# tricorder-featherwing-mk-1_6.net
KiCad netlist of a schematic drawn in EAGLE
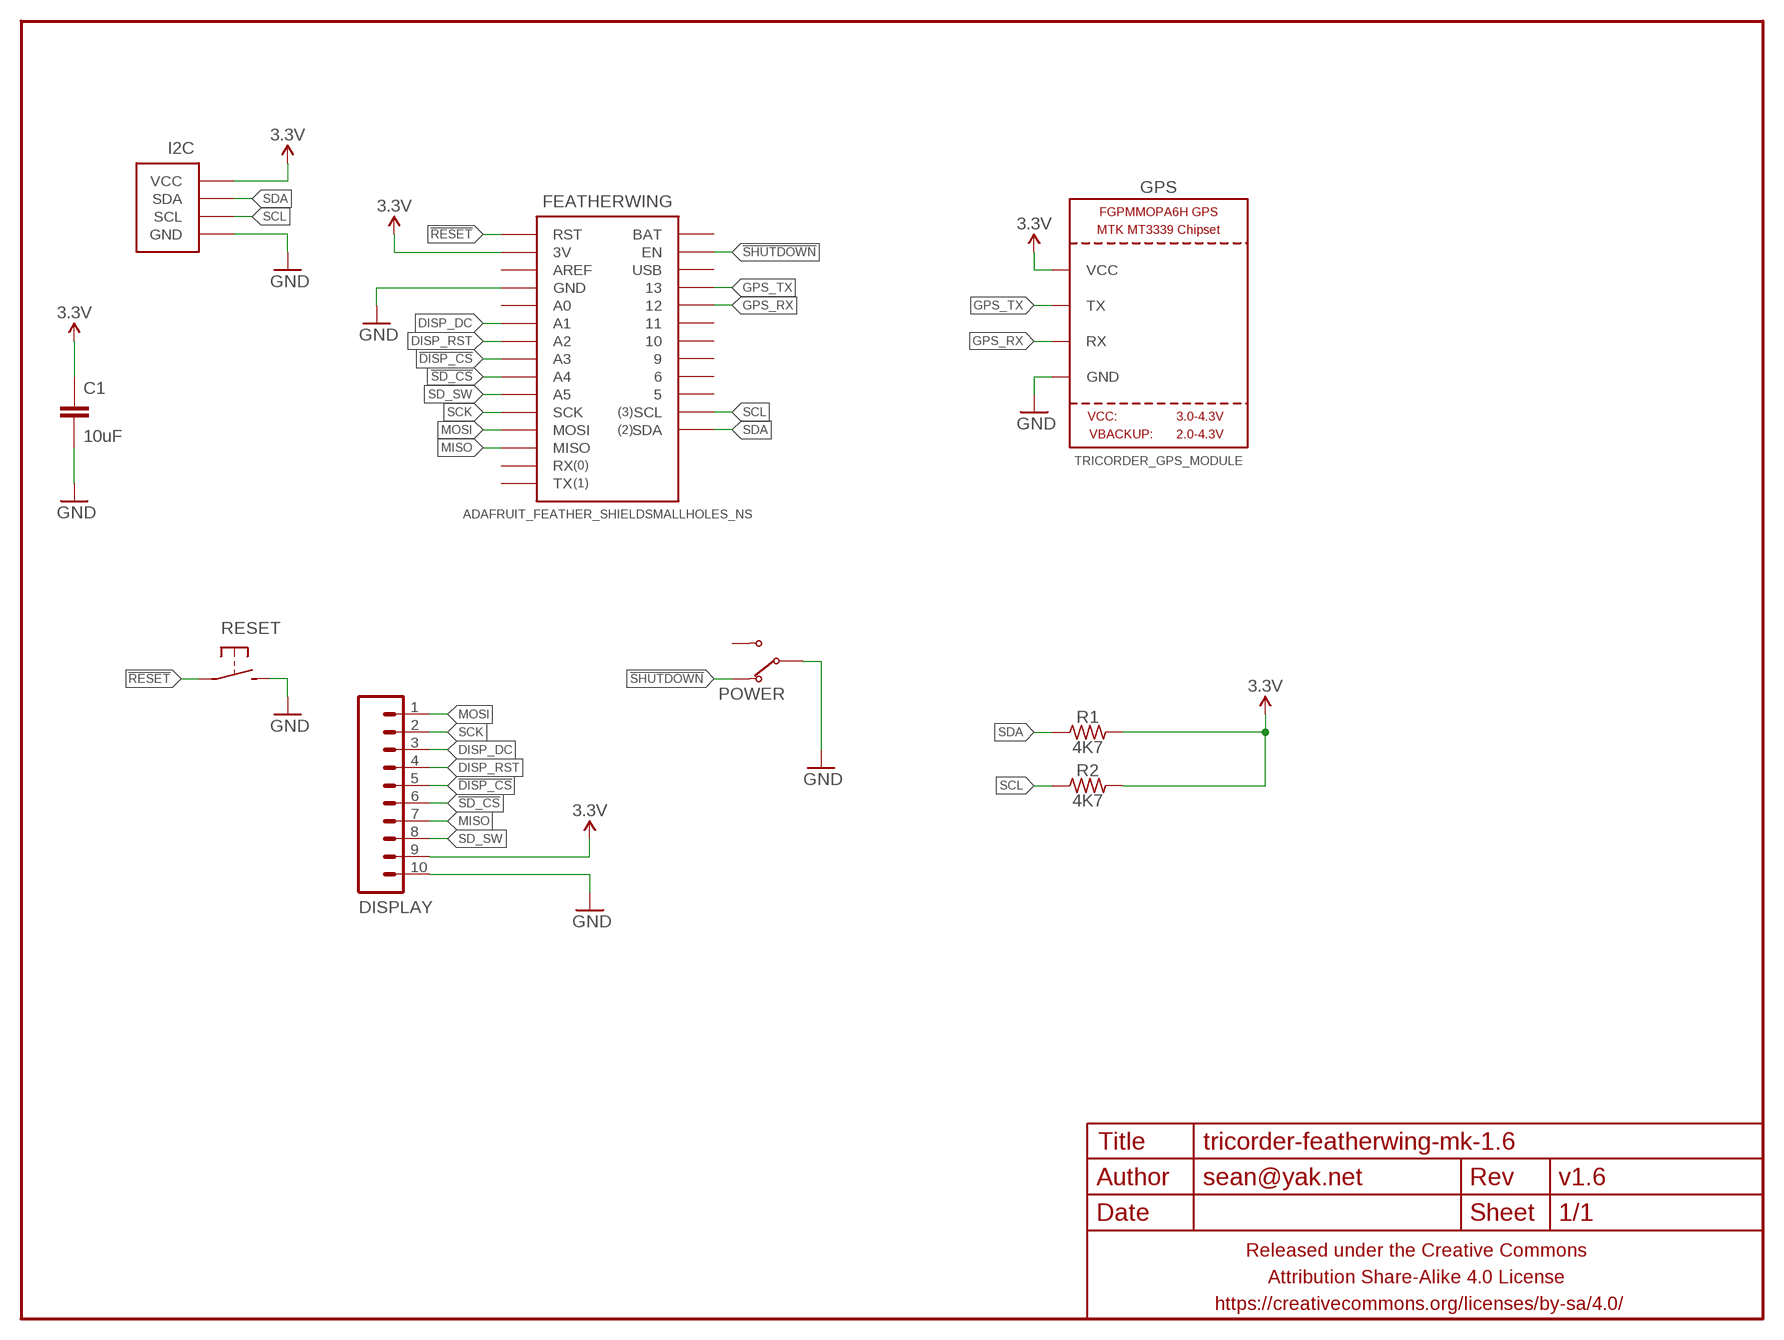
[diagram p0: schematic, sheet 1]

(export (version "E")
  (design (tool "Eeschema 10.0.6"))
  (components
    (comp (ref "C1")
      (value "10uF")
      (footprint "eagle-import:C1210")
      (libsource (lib "eagle-import") (part "CAPACITOR-CERAMICC1210"))
    )
    (comp (ref "DISPLAY")
      (value "M102MM")
      (footprint "eagle-import:1X10-2MM")
      (libsource (lib "eagle-import") (part "M102MM"))
    )
    (comp (ref "FEATHERWING")
      (value "ADAFRUIT_FEATHER_SHIELDSMALLHOLES_NS")
      (footprint "eagle-import:ADAFRUIT_FEATHER_SMALLHOLES_NS")
      (libsource (lib "eagle-import") (part "ADAFRUIT_FEATHER_SHIELDSMALLHOLES_NS"))
    )
    (comp (ref "FRAME1")
      (value "FRAME-LETTERNO_PACKAGE")
      (footprint "eagle-import:DUMMY")
      (fields (field (name "DESIGNER") "sean@yak.net") (field (name "VERSION") "v1.6"))
      (libsource (lib "eagle-import") (part "FRAME-LETTERNO_PACKAGE"))
    )
    (comp (ref "GPS")
      (value "TRICORDER_GPS_MODULE")
      (footprint "eagle-import:TRICORDER_GPS_MODULE")
      (libsource (lib "eagle-import") (part "TRICORDER_GPS_MODULE"))
    )
    (comp (ref "I2C")
      (value "M04-I2CPTH-2MM-CENTERED")
      (footprint "eagle-import:1X04-2MM-CENTERED-I2C")
      (libsource (lib "eagle-import") (part "M04-I2CPTH-2MM-CENTERED"))
    )
    (comp (ref "POWER")
      (value "SWITCH-SPDTPTH-RA-2.54MM-CENTERED")
      (footprint "eagle-import:SPDT-RA-2.54MM-CENTERED")
      (libsource (lib "eagle-import") (part "SWITCH-SPDTPTH-RA-2.54MM-CENTERED"))
    )
    (comp (ref "R1")
      (value "4K7")
      (footprint "eagle-import:R0603")
      (libsource (lib "eagle-import") (part "RESISTORR0603"))
    )
    (comp (ref "R2")
      (value "4K7")
      (footprint "eagle-import:R0603")
      (libsource (lib "eagle-import") (part "RESISTORR0603"))
    )
    (comp (ref "RESET")
      (value "SPST-NO-TACTCK-PTS840-GK")
      (footprint "eagle-import:TACTILE-SMD-CK-PTS840-GK")
      (libsource (lib "eagle-import") (part "SPST-NO-TACTCK-PTS840-GK"))
    )
  )
  (nets
    (net (code "1") (name "/~{DISP_CS}") (class "Default")
      (node (ref "DISPLAY") (pin "5") (pinfunction "5_5") (pintype "passive"))
      (node (ref "FEATHERWING") (pin "A3") (pinfunction "A3_A3") (pintype "bidirectional"))
    )
    (net (code "2") (name "/~{RESET}") (class "Default")
      (node (ref "FEATHERWING") (pin "RST") (pinfunction "RST_RST") (pintype "bidirectional"))
      (node (ref "RESET") (pin "1") (pinfunction "1_1") (pintype "passive"))
      (node (ref "RESET") (pin "2") (pinfunction "1_2") (pintype "passive"))
    )
    (net (code "3") (name "/~{SD_CS}") (class "Default")
      (node (ref "DISPLAY") (pin "6") (pinfunction "6_6") (pintype "passive"))
      (node (ref "FEATHERWING") (pin "A4") (pinfunction "A4_A4") (pintype "bidirectional"))
    )
    (net (code "4") (name "/~{SHUTDOWN}") (class "Default")
      (node (ref "FEATHERWING") (pin "EN") (pinfunction "EN_EN") (pintype "bidirectional"))
      (node (ref "POWER") (pin "1") (pinfunction "NC_1") (pintype "passive"))
    )
    (net (code "5") (name "3.3V") (class "Default")
      (node (ref "C1") (pin "1") (pinfunction "1_1") (pintype "passive"))
      (node (ref "DISPLAY") (pin "9") (pinfunction "9_9") (pintype "passive"))
      (node (ref "FEATHERWING") (pin "3V") (pinfunction "3V_3V") (pintype "bidirectional"))
      (node (ref "GPS") (pin "VCC") (pinfunction "VCC_VCC") (pintype "bidirectional"))
      (node (ref "I2C") (pin "2") (pinfunction "VCC_2") (pintype "bidirectional"))
      (node (ref "R1") (pin "2") (pinfunction "2_2") (pintype "passive"))
      (node (ref "R2") (pin "2") (pinfunction "2_2") (pintype "passive"))
    )
    (net (code "6") (name "DISP_DC") (class "Default")
      (node (ref "DISPLAY") (pin "3") (pinfunction "3_3") (pintype "passive"))
      (node (ref "FEATHERWING") (pin "A1") (pinfunction "A1_A1") (pintype "bidirectional"))
    )
    (net (code "7") (name "DISP_RST") (class "Default")
      (node (ref "DISPLAY") (pin "4") (pinfunction "4_4") (pintype "passive"))
      (node (ref "FEATHERWING") (pin "A2") (pinfunction "A2_A2") (pintype "bidirectional"))
    )
    (net (code "8") (name "GND") (class "Default")
      (node (ref "C1") (pin "2") (pinfunction "2_2") (pintype "passive"))
      (node (ref "DISPLAY") (pin "10") (pinfunction "10_10") (pintype "passive"))
      (node (ref "FEATHERWING") (pin "GND@0") (pinfunction "GND_GND@0") (pintype "bidirectional"))
      (node (ref "FEATHERWING") (pin "GND@1") (pinfunction "GND_GND@1") (pintype "bidirectional"))
      (node (ref "GPS") (pin "GND@1") (pinfunction "GND_GND@1") (pintype "bidirectional"))
      (node (ref "GPS") (pin "GND@2") (pinfunction "GND_GND@2") (pintype "bidirectional"))
      (node (ref "I2C") (pin "1") (pinfunction "GND_1") (pintype "bidirectional"))
      (node (ref "POWER") (pin "2") (pinfunction "COM_2") (pintype "passive"))
      (node (ref "RESET") (pin "3") (pinfunction "2_3") (pintype "passive"))
      (node (ref "RESET") (pin "4") (pinfunction "2_4") (pintype "passive"))
    )
    (net (code "9") (name "GPS_RX") (class "Default")
      (node (ref "FEATHERWING") (pin "12") (pinfunction "12_12") (pintype "bidirectional"))
      (node (ref "GPS") (pin "RX") (pinfunction "RX_RX") (pintype "bidirectional"))
    )
    (net (code "10") (name "GPS_TX") (class "Default")
      (node (ref "FEATHERWING") (pin "13") (pinfunction "13_13") (pintype "bidirectional"))
      (node (ref "GPS") (pin "TX") (pinfunction "TX_TX") (pintype "bidirectional"))
    )
    (net (code "11") (name "MISO") (class "Default")
      (node (ref "DISPLAY") (pin "7") (pinfunction "7_7") (pintype "passive"))
      (node (ref "FEATHERWING") (pin "MISO") (pinfunction "MISO_MISO") (pintype "bidirectional"))
    )
    (net (code "12") (name "MOSI") (class "Default")
      (node (ref "DISPLAY") (pin "1") (pinfunction "1_1") (pintype "passive"))
      (node (ref "FEATHERWING") (pin "MOSI") (pinfunction "MOSI_MOSI") (pintype "bidirectional"))
    )
    (net (code "13") (name "SCK") (class "Default")
      (node (ref "DISPLAY") (pin "2") (pinfunction "2_2") (pintype "passive"))
      (node (ref "FEATHERWING") (pin "SCK") (pinfunction "SCK_SCK") (pintype "bidirectional"))
    )
    (net (code "14") (name "SCL") (class "Default")
      (node (ref "FEATHERWING") (pin "SCL") (pinfunction "SCL_SCL") (pintype "bidirectional"))
      (node (ref "I2C") (pin "4") (pinfunction "SCL_4") (pintype "bidirectional"))
      (node (ref "R2") (pin "1") (pinfunction "1_1") (pintype "passive"))
    )
    (net (code "15") (name "SDA") (class "Default")
      (node (ref "FEATHERWING") (pin "SDA") (pinfunction "SDA_SDA") (pintype "bidirectional"))
      (node (ref "I2C") (pin "3") (pinfunction "SDA_3") (pintype "bidirectional"))
      (node (ref "R1") (pin "1") (pinfunction "1_1") (pintype "passive"))
    )
    (net (code "16") (name "SD_SW") (class "Default")
      (node (ref "DISPLAY") (pin "8") (pinfunction "8_8") (pintype "passive"))
      (node (ref "FEATHERWING") (pin "A5") (pinfunction "A5_A5") (pintype "bidirectional"))
    )
    (net (code "17") (name "unconnected-(FEATHERWING-Pad5)") (class "Default")
      (node (ref "FEATHERWING") (pin "5") (pinfunction "5_5") (pintype "bidirectional"))
    )
    (net (code "18") (name "unconnected-(FEATHERWING-Pad6)") (class "Default")
      (node (ref "FEATHERWING") (pin "6") (pinfunction "6_6") (pintype "bidirectional"))
    )
    (net (code "19") (name "unconnected-(FEATHERWING-Pad9)") (class "Default")
      (node (ref "FEATHERWING") (pin "9") (pinfunction "9_9") (pintype "bidirectional"))
    )
    (net (code "20") (name "unconnected-(FEATHERWING-Pad10)") (class "Default")
      (node (ref "FEATHERWING") (pin "10") (pinfunction "10_10") (pintype "bidirectional"))
    )
    (net (code "21") (name "unconnected-(FEATHERWING-Pad11)") (class "Default")
      (node (ref "FEATHERWING") (pin "11") (pinfunction "11_11") (pintype "bidirectional"))
    )
    (net (code "22") (name "unconnected-(FEATHERWING-PadA0)") (class "Default")
      (node (ref "FEATHERWING") (pin "A0") (pinfunction "A0_A0") (pintype "bidirectional"))
    )
    (net (code "23") (name "unconnected-(FEATHERWING-PadAREF)") (class "Default")
      (node (ref "FEATHERWING") (pin "AREF") (pinfunction "AREF_AREF") (pintype "bidirectional"))
    )
    (net (code "24") (name "unconnected-(FEATHERWING-PadBAT)") (class "Default")
      (node (ref "FEATHERWING") (pin "BAT") (pinfunction "BAT_BAT") (pintype "bidirectional"))
    )
    (net (code "25") (name "unconnected-(FEATHERWING-PadRX)") (class "Default")
      (node (ref "FEATHERWING") (pin "RX") (pinfunction "RX_RX") (pintype "bidirectional"))
    )
    (net (code "26") (name "unconnected-(FEATHERWING-PadTX)") (class "Default")
      (node (ref "FEATHERWING") (pin "TX") (pinfunction "TX_TX") (pintype "bidirectional"))
    )
    (net (code "27") (name "unconnected-(FEATHERWING-PadUSB)") (class "Default")
      (node (ref "FEATHERWING") (pin "USB") (pinfunction "USB_USB") (pintype "bidirectional"))
    )
    (net (code "28") (name "unconnected-(POWER-NO-Pad3)") (class "Default")
      (node (ref "POWER") (pin "3") (pinfunction "NO_3") (pintype "passive"))
    )
  )
)
